# TPS74401RGWRM3.net
KiCad netlist of a schematic drawn in Altium Designer
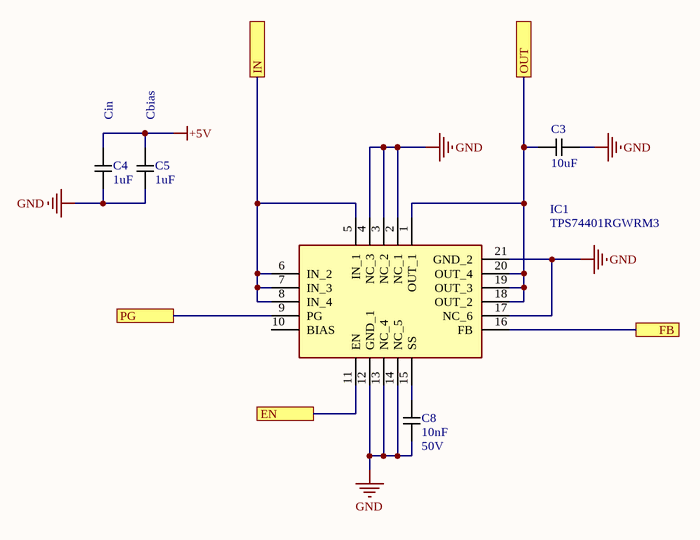
[diagram p0: TPS74401RGWRM3.SchDoc]

(export (version "E")
  (design (tool "Eeschema 10.0.6"))
  (components
    (comp (ref "C3")
      (value "10uF")
      (footprint "C0603_MD")
      (description "CAP CER 10UF 16V 20% X6S 0603")
      (fields (field (name "MANUFACTURER") "Murata Electronics North America") (field (name "VOLTAGE") "16V"))
      (libsource (lib "Capacitor") (part "GRM188C81C106MA73D"))
    )
    (comp (ref "C4")
      (value "Cin")
      (footprint "C0603_MD")
      (description "CAP CER 1UF 50V 10% X5R 0603")
      (fields
        (field (name "MANUFACTURER") "Taiyo Yuden")
        (field (name "VOLTAGE") "50V")
        (field (name "ALTIUM_VALUE") "1uF")
      )
      (libsource (lib "Capacitor") (part "UMK107BJ105KA-T"))
    )
    (comp (ref "C5")
      (value "Cbias")
      (footprint "C0603_MD")
      (description "CAP CER 1UF 50V 10% X5R 0603")
      (fields
        (field (name "MANUFACTURER") "Taiyo Yuden")
        (field (name "VOLTAGE") "50V")
        (field (name "ALTIUM_VALUE") "1uF")
      )
      (libsource (lib "Capacitor") (part "UMK107BJ105KA-T"))
    )
    (comp (ref "C8")
      (value "10nF")
      (footprint "C0603_MD")
      (description "10000pF 50V Ceramic Capacitor X7R 0603")
      (fields
        (field (name "MANUFACTURER") "Samsung Electro-Mechanics America, Inc.")
        (field (name "VOLTAGE") "50V")
        (field (name "Comment") "CL10B103KB8NNNC")
      )
      (libsource (lib "Capacitor") (part "CL10B103KB8NNNC"))
    )
    (comp (ref "IC1")
      (value "TPS74401RGWRM3")
      (footprint "SamacSys:QFN65P500X500X100-21N-D")
      (description "Integrated Circuit")
      (fields (field (name "MOUSER PART NUMBER") "595-TPS74401RGWRM3"))
      (libsource (lib "*") (part "TPS74401RGWRM3"))
    )
  )
  (nets
    (net (code "1") (name "+5V") (class "Default")
      (node (ref "C4") (pin "1") (pinfunction "1_1") (pintype "passive"))
      (node (ref "C5") (pin "1") (pinfunction "1_1") (pintype "passive"))
    )
    (net (code "2") (name "/EN") (class "Default")
      (node (ref "IC1") (pin "11") (pinfunction "EN_11") (pintype "passive"))
    )
    (net (code "3") (name "/FB") (class "Default")
      (node (ref "IC1") (pin "16") (pinfunction "FB_16") (pintype "passive"))
    )
    (net (code "4") (name "/IN") (class "Default")
      (node (ref "IC1") (pin "5") (pinfunction "IN_1_5") (pintype "passive"))
      (node (ref "IC1") (pin "6") (pinfunction "IN_2_6") (pintype "passive"))
      (node (ref "IC1") (pin "7") (pinfunction "IN_3_7") (pintype "passive"))
      (node (ref "IC1") (pin "8") (pinfunction "IN_4_8") (pintype "passive"))
    )
    (net (code "5") (name "/OUT") (class "Default")
      (node (ref "C3") (pin "2") (pinfunction "2_2") (pintype "passive"))
      (node (ref "IC1") (pin "1") (pinfunction "OUT_1_1") (pintype "passive"))
      (node (ref "IC1") (pin "18") (pinfunction "OUT_2_18") (pintype "passive"))
      (node (ref "IC1") (pin "19") (pinfunction "OUT_3_19") (pintype "passive"))
      (node (ref "IC1") (pin "20") (pinfunction "OUT_4_20") (pintype "passive"))
    )
    (net (code "6") (name "/PG") (class "Default")
      (node (ref "IC1") (pin "9") (pinfunction "PG_9") (pintype "passive"))
    )
    (net (code "7") (name "GND") (class "Default")
      (node (ref "C3") (pin "1") (pinfunction "1_1") (pintype "passive"))
      (node (ref "C4") (pin "2") (pinfunction "2_2") (pintype "passive"))
      (node (ref "C5") (pin "2") (pinfunction "2_2") (pintype "passive"))
      (node (ref "C8") (pin "2") (pinfunction "2_2") (pintype "passive"))
      (node (ref "IC1") (pin "12") (pinfunction "GND_1_12") (pintype "passive"))
      (node (ref "IC1") (pin "13") (pinfunction "NC_4_13") (pintype "passive"))
      (node (ref "IC1") (pin "14") (pinfunction "NC_5_14") (pintype "passive"))
      (node (ref "IC1") (pin "17") (pinfunction "NC_6_17") (pintype "passive"))
      (node (ref "IC1") (pin "2") (pinfunction "NC_1_2") (pintype "passive"))
      (node (ref "IC1") (pin "21") (pinfunction "GND_2_21") (pintype "passive"))
      (node (ref "IC1") (pin "3") (pinfunction "NC_2_3") (pintype "passive"))
      (node (ref "IC1") (pin "4") (pinfunction "NC_3_4") (pintype "passive"))
    )
    (net (code "8") (name "Net-(IC1-SS)") (class "Default")
      (node (ref "C8") (pin "1") (pinfunction "1_1") (pintype "passive"))
      (node (ref "IC1") (pin "15") (pinfunction "SS_15") (pintype "passive"))
    )
    (net (code "9") (name "unconnected-(IC1-BIAS-Pad10)") (class "Default")
      (node (ref "IC1") (pin "10") (pinfunction "BIAS_10") (pintype "passive"))
    )
  )
)
